# H.net
KiCad netlist of a schematic drawn in Altium Designer
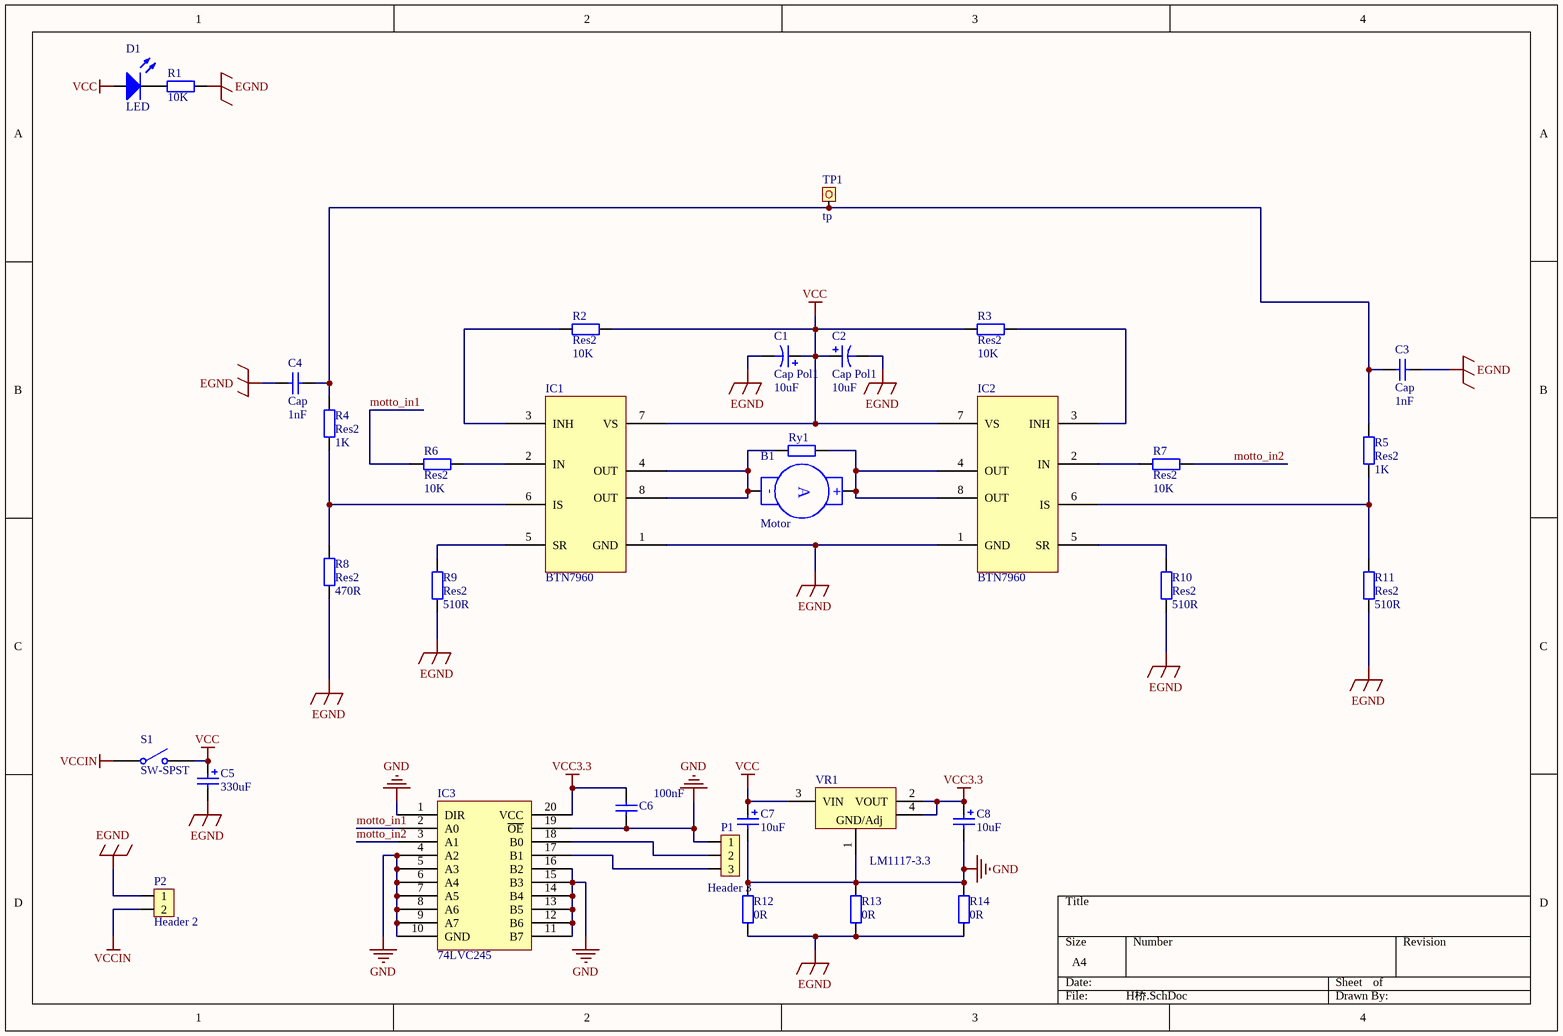
[diagram p0: H桥.SchDoc]

(export (version "E")
  (design (tool "Eeschema 10.0.6"))
  (components
    (comp (ref "B1")
      (value "Motor")
      (footprint "KF301-2P")
      (description "Servo Motor")
      (libsource (lib "Landzo") (part "Motor Servo"))
    )
    (comp (ref "C1")
      (value "Cap Pol1")
      (footprint "1206(2)")
      (description "Polarized Capacitor (Radial)")
      (fields (field (name "ALTIUM_VALUE") "10uF") (field (name "PUBLISHER") "Altium Limited"))
      (libsource (lib "Miscellaneous Devices") (part "Cap Pol1"))
    )
    (comp (ref "C2")
      (value "Cap Pol1")
      (footprint "1206(2)")
      (description "Polarized Capacitor (Radial)")
      (fields (field (name "ALTIUM_VALUE") "10uF") (field (name "PUBLISHER") "Altium Limited"))
      (libsource (lib "Miscellaneous Devices") (part "Cap Pol1"))
    )
    (comp (ref "C3")
      (value "Cap")
      (footprint "1206(2)")
      (description "Capacitor")
      (fields (field (name "ALTIUM_VALUE") "1nF") (field (name "PUBLISHER") "Altium Limited"))
      (libsource (lib "Miscellaneous Devices") (part "Cap"))
    )
    (comp (ref "C4")
      (value "Cap")
      (footprint "1206(2)")
      (description "Capacitor")
      (fields (field (name "ALTIUM_VALUE") "1nF") (field (name "PUBLISHER") "Altium Limited"))
      (libsource (lib "Miscellaneous Devices") (part "Cap"))
    )
    (comp (ref "C5")
      (value "330uF")
      (footprint "Inductor/8mm")
      (description "Polarized Capacitor (Radial)")
      (libsource (lib "Landzo") (part "Cap Pol1"))
    )
    (comp (ref "C6")
      (value "100nF")
      (footprint "1206(2)")
      (description "Capacitor")
      (libsource (lib "Landzo") (part "Cap"))
    )
    (comp (ref "C7")
      (value "10uF")
      (footprint "1206(2)")
      (description "Polarized Capacitor (Radial)")
      (libsource (lib "Landzo") (part "Cap Pol1"))
    )
    (comp (ref "C8")
      (value "10uF")
      (footprint "1206(2)")
      (description "Polarized Capacitor (Radial)")
      (libsource (lib "Landzo") (part "Cap Pol1"))
    )
    (comp (ref "D1")
      (value "LED")
      (footprint "1206(2)")
      (description "Typical INFRARED GaAs LED")
      (libsource (lib "Landzo") (part "LED"))
    )
    (comp (ref "IC1") (value "BTN7960") (footprint "PG-TO263-7-1") (libsource (lib "") (part "BTN7960_1")))
    (comp (ref "IC2")
      (value "BTN7960")
      (footprint "PG-TO263-7-1")
      (libsource (lib "Landzo") (part "BTN7960"))
    )
    (comp (ref "IC3")
      (value "74LVC245")
      (footprint "TSSOP20 74lvc245")
      (libsource (lib "Landzo") (part "74LVC245"))
    )
    (comp (ref "P1")
      (value "Header 3")
      (footprint "XH2.54_3P")
      (description "Header, 3-Pin")
      (libsource (lib "Landzo") (part "Header 3"))
    )
    (comp (ref "P2")
      (value "Header 2")
      (footprint "KF301-2P")
      (description "Header, 2-Pin")
      (libsource (lib "Landzo") (part "Header 2"))
    )
    (comp (ref "R1")
      (value "10K")
      (footprint "1206(2)")
      (description "Resistor")
      (libsource (lib "") (part "Res_2"))
    )
    (comp (ref "R2")
      (value "Res2")
      (footprint "1206(2)")
      (description "Resistor")
      (fields (field (name "ALTIUM_VALUE") "10K") (field (name "PUBLISHER") "Altium Limited"))
      (libsource (lib "Miscellaneous Devices") (part "Res2"))
    )
    (comp (ref "R3")
      (value "Res2")
      (footprint "1206(2)")
      (description "Resistor")
      (fields (field (name "ALTIUM_VALUE") "10K") (field (name "PUBLISHER") "Altium Limited"))
      (libsource (lib "Miscellaneous Devices") (part "Res2"))
    )
    (comp (ref "R4")
      (value "Res2")
      (footprint "1206(2)")
      (description "Resistor")
      (fields (field (name "ALTIUM_VALUE") "1K") (field (name "PUBLISHER") "Altium Limited"))
      (libsource (lib "") (part "Res2_1"))
    )
    (comp (ref "R5")
      (value "Res2")
      (footprint "1206(2)")
      (description "Resistor")
      (fields (field (name "ALTIUM_VALUE") "1K") (field (name "PUBLISHER") "Altium Limited"))
      (libsource (lib "") (part "Res2_1"))
    )
    (comp (ref "R6")
      (value "Res2")
      (footprint "1206(2)")
      (description "Resistor")
      (fields (field (name "ALTIUM_VALUE") "10K") (field (name "PUBLISHER") "Altium Limited"))
      (libsource (lib "Miscellaneous Devices") (part "Res2"))
    )
    (comp (ref "R7")
      (value "Res2")
      (footprint "1206(2)")
      (description "Resistor")
      (fields (field (name "ALTIUM_VALUE") "10K") (field (name "PUBLISHER") "Altium Limited"))
      (libsource (lib "Miscellaneous Devices") (part "Res2"))
    )
    (comp (ref "R8")
      (value "Res2")
      (footprint "1206(2)")
      (description "Resistor")
      (fields (field (name "ALTIUM_VALUE") "470R") (field (name "PUBLISHER") "Altium Limited"))
      (libsource (lib "") (part "Res2_1"))
    )
    (comp (ref "R9")
      (value "Res2")
      (footprint "1206(2)")
      (description "Resistor")
      (fields (field (name "ALTIUM_VALUE") "510R") (field (name "PUBLISHER") "Altium Limited"))
      (libsource (lib "") (part "Res2_1"))
    )
    (comp (ref "R10")
      (value "Res2")
      (footprint "1206(2)")
      (description "Resistor")
      (fields (field (name "ALTIUM_VALUE") "510R") (field (name "PUBLISHER") "Altium Limited"))
      (libsource (lib "") (part "Res2_1"))
    )
    (comp (ref "R11")
      (value "Res2")
      (footprint "1206(2)")
      (description "Resistor")
      (fields (field (name "ALTIUM_VALUE") "510R") (field (name "PUBLISHER") "Altium Limited"))
      (libsource (lib "") (part "Res2_1"))
    )
    (comp (ref "R12")
      (value "0R")
      (footprint "1206(2)")
      (description "Resistor")
      (libsource (lib "") (part "Res_1"))
    )
    (comp (ref "R13")
      (value "0R")
      (footprint "1206(2)")
      (description "Resistor")
      (libsource (lib "") (part "Res_1"))
    )
    (comp (ref "R14")
      (value "0R")
      (footprint "1206(2)")
      (description "Resistor")
      (libsource (lib "") (part "Res_1"))
    )
    (comp (ref "Ry1")
      (value "~")
      (footprint "1206(2)")
      (description "Resistor")
      (libsource (lib "Landzo") (part "Res"))
    )
    (comp (ref "S1")
      (value "SW-SPST")
      (footprint "switch-black")
      (description "Single-Pole, Single-Throw Switch")
      (fields (field (name "PUBLISHER") "Altium Limited"))
      (libsource (lib "Miscellaneous Devices") (part "SW-SPST"))
    )
    (comp (ref "TP1") (value "tp") (footprint "TP1") (libsource (lib "Landzo") (part "TP")))
    (comp (ref "VR1")
      (value "LM1117-3.3")
      (footprint "SOT-223")
      (description "Voltage Regulator")
      (libsource (lib "Landzo") (part "Volt_Reg_1117"))
    )
  )
  (nets
    (net (code "1") (name "/motto_in1") (class "Default")
      (node (ref "IC3") (pin "2") (pinfunction "A0_2") (pintype "passive"))
      (node (ref "R6") (pin "1") (pinfunction "1_1") (pintype "passive"))
    )
    (net (code "2") (name "/motto_in2") (class "Default")
      (node (ref "IC3") (pin "3") (pinfunction "A1_3") (pintype "passive"))
      (node (ref "R7") (pin "2") (pinfunction "2_2") (pintype "passive"))
    )
    (net (code "3") (name "EGND") (class "Default")
      (node (ref "C1") (pin "2") (pinfunction "2_2") (pintype "passive"))
      (node (ref "C2") (pin "2") (pinfunction "2_2") (pintype "passive"))
      (node (ref "C3") (pin "1") (pinfunction "1_1") (pintype "passive"))
      (node (ref "C4") (pin "1") (pinfunction "1_1") (pintype "passive"))
      (node (ref "C5") (pin "2") (pinfunction "2_2") (pintype "passive"))
      (node (ref "IC1") (pin "1") (pinfunction "GND_1") (pintype "passive"))
      (node (ref "IC2") (pin "1") (pinfunction "GND_1") (pintype "passive"))
      (node (ref "P2") (pin "1") (pinfunction "1_1") (pintype "passive"))
      (node (ref "R1") (pin "1") (pinfunction "1_1") (pintype "passive"))
      (node (ref "R10") (pin "1") (pinfunction "1_1") (pintype "passive"))
      (node (ref "R11") (pin "1") (pinfunction "1_1") (pintype "passive"))
      (node (ref "R12") (pin "1") (pinfunction "1_1") (pintype "passive"))
      (node (ref "R13") (pin "1") (pinfunction "1_1") (pintype "passive"))
      (node (ref "R14") (pin "1") (pinfunction "1_1") (pintype "passive"))
      (node (ref "R8") (pin "1") (pinfunction "1_1") (pintype "passive"))
      (node (ref "R9") (pin "1") (pinfunction "1_1") (pintype "passive"))
    )
    (net (code "4") (name "GND") (class "Default")
      (node (ref "C6") (pin "1") (pinfunction "1_1") (pintype "passive"))
      (node (ref "C7") (pin "2") (pinfunction "2_2") (pintype "passive"))
      (node (ref "C8") (pin "2") (pinfunction "2_2") (pintype "passive"))
      (node (ref "IC3") (pin "1") (pinfunction "DIR_1") (pintype "passive"))
      (node (ref "IC3") (pin "10") (pinfunction "GND_10") (pintype "passive"))
      (node (ref "IC3") (pin "11") (pinfunction "B7_11") (pintype "passive"))
      (node (ref "IC3") (pin "12") (pinfunction "B6_12") (pintype "passive"))
      (node (ref "IC3") (pin "13") (pinfunction "B5_13") (pintype "passive"))
      (node (ref "IC3") (pin "14") (pinfunction "B4_14") (pintype "passive"))
      (node (ref "IC3") (pin "15") (pinfunction "B3_15") (pintype "passive"))
      (node (ref "IC3") (pin "16") (pinfunction "B2_16") (pintype "passive"))
      (node (ref "IC3") (pin "19") (pinfunction "~{OE}_19") (pintype "passive"))
      (node (ref "IC3") (pin "4") (pinfunction "A2_4") (pintype "passive"))
      (node (ref "IC3") (pin "5") (pinfunction "A3_5") (pintype "passive"))
      (node (ref "IC3") (pin "6") (pinfunction "A4_6") (pintype "passive"))
      (node (ref "IC3") (pin "7") (pinfunction "A5_7") (pintype "passive"))
      (node (ref "IC3") (pin "8") (pinfunction "A6_8") (pintype "passive"))
      (node (ref "IC3") (pin "9") (pinfunction "A7_9") (pintype "passive"))
      (node (ref "P1") (pin "1") (pinfunction "1_1") (pintype "passive"))
      (node (ref "R12") (pin "2") (pinfunction "2_2") (pintype "passive"))
      (node (ref "R13") (pin "2") (pinfunction "2_2") (pintype "passive"))
      (node (ref "R14") (pin "2") (pinfunction "2_2") (pintype "passive"))
      (node (ref "VR1") (pin "1") (pinfunction "GND/Adj_1") (pintype "passive"))
    )
    (net (code "5") (name "Net-(B1-+)") (class "Default")
      (node (ref "B1") (pin "1") (pinfunction "+_1") (pintype "passive"))
      (node (ref "IC2") (pin "4") (pinfunction "OUT_4") (pintype "passive"))
      (node (ref "IC2") (pin "8") (pinfunction "OUT_8") (pintype "passive"))
      (node (ref "Ry1") (pin "2") (pinfunction "2_2") (pintype "passive"))
    )
    (net (code "6") (name "Net-(B1--)") (class "Default")
      (node (ref "B1") (pin "2") (pinfunction "-_2") (pintype "passive"))
      (node (ref "IC1") (pin "4") (pinfunction "OUT_4") (pintype "passive"))
      (node (ref "IC1") (pin "8") (pinfunction "OUT_8") (pintype "passive"))
      (node (ref "Ry1") (pin "1") (pinfunction "1_1") (pintype "passive"))
    )
    (net (code "7") (name "Net-(C3-Pad2)") (class "Default")
      (node (ref "C3") (pin "2") (pinfunction "2_2") (pintype "passive"))
      (node (ref "C4") (pin "2") (pinfunction "2_2") (pintype "passive"))
      (node (ref "R4") (pin "2") (pinfunction "2_2") (pintype "passive"))
      (node (ref "R5") (pin "2") (pinfunction "2_2") (pintype "passive"))
      (node (ref "TP1") (pin "1") (pinfunction "1_1") (pintype "passive"))
    )
    (net (code "8") (name "Net-(D1-Pad2)") (class "Default")
      (node (ref "D1") (pin "2") (pinfunction "2_2") (pintype "passive"))
      (node (ref "R1") (pin "2") (pinfunction "2_2") (pintype "passive"))
    )
    (net (code "9") (name "Net-(IC1-IN)") (class "Default")
      (node (ref "IC1") (pin "2") (pinfunction "IN_2") (pintype "passive"))
      (node (ref "R6") (pin "2") (pinfunction "2_2") (pintype "passive"))
    )
    (net (code "10") (name "Net-(IC1-INH)") (class "Default")
      (node (ref "IC1") (pin "3") (pinfunction "INH_3") (pintype "passive"))
      (node (ref "R2") (pin "1") (pinfunction "1_1") (pintype "passive"))
    )
    (net (code "11") (name "Net-(IC1-IS)") (class "Default")
      (node (ref "IC1") (pin "6") (pinfunction "IS_6") (pintype "passive"))
      (node (ref "R4") (pin "1") (pinfunction "1_1") (pintype "passive"))
      (node (ref "R8") (pin "2") (pinfunction "2_2") (pintype "passive"))
    )
    (net (code "12") (name "Net-(IC1-SR)") (class "Default")
      (node (ref "IC1") (pin "5") (pinfunction "SR_5") (pintype "passive"))
      (node (ref "R9") (pin "2") (pinfunction "2_2") (pintype "passive"))
    )
    (net (code "13") (name "Net-(IC2-IN)") (class "Default")
      (node (ref "IC2") (pin "2") (pinfunction "IN_2") (pintype "passive"))
      (node (ref "R7") (pin "1") (pinfunction "1_1") (pintype "passive"))
    )
    (net (code "14") (name "Net-(IC2-INH)") (class "Default")
      (node (ref "IC2") (pin "3") (pinfunction "INH_3") (pintype "passive"))
      (node (ref "R3") (pin "2") (pinfunction "2_2") (pintype "passive"))
    )
    (net (code "15") (name "Net-(IC2-IS)") (class "Default")
      (node (ref "IC2") (pin "6") (pinfunction "IS_6") (pintype "passive"))
      (node (ref "R11") (pin "2") (pinfunction "2_2") (pintype "passive"))
      (node (ref "R5") (pin "1") (pinfunction "1_1") (pintype "passive"))
    )
    (net (code "16") (name "Net-(IC2-SR)") (class "Default")
      (node (ref "IC2") (pin "5") (pinfunction "SR_5") (pintype "passive"))
      (node (ref "R10") (pin "2") (pinfunction "2_2") (pintype "passive"))
    )
    (net (code "17") (name "Net-(IC3-B0)") (class "Default")
      (node (ref "IC3") (pin "18") (pinfunction "B0_18") (pintype "passive"))
      (node (ref "P1") (pin "2") (pinfunction "2_2") (pintype "passive"))
    )
    (net (code "18") (name "Net-(IC3-B1)") (class "Default")
      (node (ref "IC3") (pin "17") (pinfunction "B1_17") (pintype "passive"))
      (node (ref "P1") (pin "3") (pinfunction "3_3") (pintype "passive"))
    )
    (net (code "19") (name "VCC") (class "Default")
      (node (ref "C1") (pin "1") (pinfunction "1_1") (pintype "passive"))
      (node (ref "C2") (pin "1") (pinfunction "1_1") (pintype "passive"))
      (node (ref "C5") (pin "1") (pinfunction "1_1") (pintype "passive"))
      (node (ref "C7") (pin "1") (pinfunction "1_1") (pintype "passive"))
      (node (ref "D1") (pin "1") (pinfunction "1_1") (pintype "passive"))
      (node (ref "IC1") (pin "7") (pinfunction "VS_7") (pintype "passive"))
      (node (ref "IC2") (pin "7") (pinfunction "VS_7") (pintype "passive"))
      (node (ref "R2") (pin "2") (pinfunction "2_2") (pintype "passive"))
      (node (ref "R3") (pin "1") (pinfunction "1_1") (pintype "passive"))
      (node (ref "S1") (pin "2") (pinfunction "NO_2") (pintype "passive"))
      (node (ref "VR1") (pin "3") (pinfunction "VIN_3") (pintype "passive"))
    )
    (net (code "20") (name "VCC3.3") (class "Default")
      (node (ref "C6") (pin "2") (pinfunction "2_2") (pintype "passive"))
      (node (ref "C8") (pin "1") (pinfunction "1_1") (pintype "passive"))
      (node (ref "IC3") (pin "20") (pinfunction "VCC_20") (pintype "passive"))
      (node (ref "VR1") (pin "2") (pinfunction "VOUT_2") (pintype "passive"))
      (node (ref "VR1") (pin "4") (pinfunction "VOUT_4") (pintype "passive"))
    )
    (net (code "21") (name "VCCIN") (class "Default")
      (node (ref "P2") (pin "2") (pinfunction "2_2") (pintype "passive"))
      (node (ref "S1") (pin "1") (pinfunction "COMMON_1") (pintype "passive"))
    )
  )
)
